# BTL_POWER.net
KiCad netlist of a schematic drawn in Altium Designer
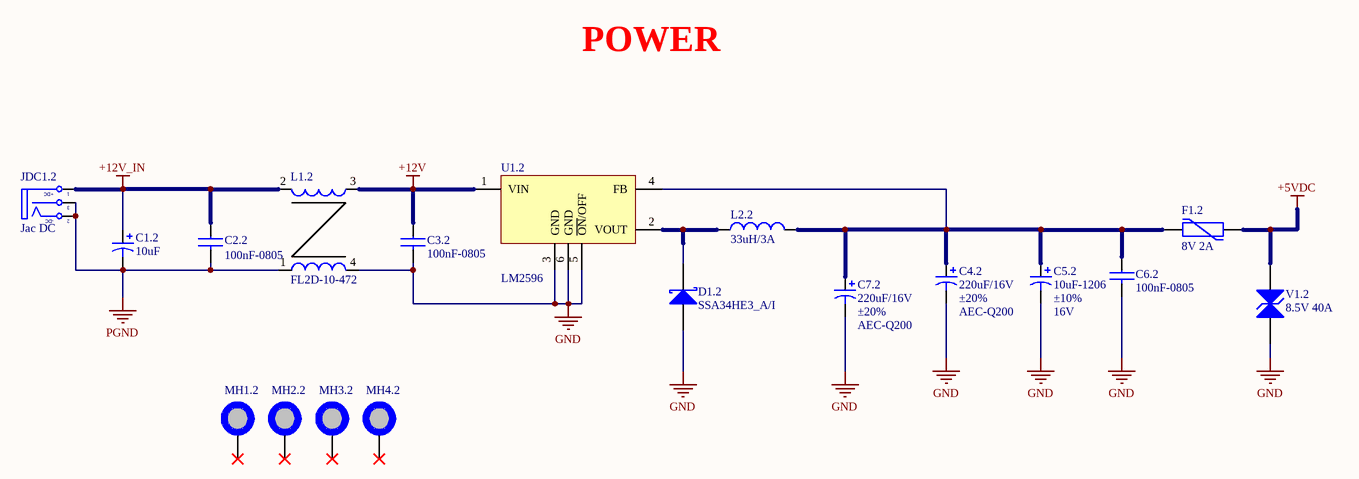
[diagram p0: BTL_POWER.SchDoc]

(export (version "E")
  (design (tool "Eeschema 10.0.6"))
  (components
    (comp (ref "C1.2")
      (value "10uF")
      (footprint "CAP_ALUMINUM_D8")
      (description "CAP ALUM 47UF 20% 16V SMD")
      (fields
        (field (name "MANUFACTURER") "Panasonic Electronic Components")
        (field (name "MANUFACTURER PART NUMBER") "EEE-FK1C470P")
      )
      (libsource (lib "Indruino") (part "EEE-FK1C470P"))
    )
    (comp (ref "C2.2")
      (value "100nF-0805")
      (footprint "CAP0805")
      (description "CAP CER 30PF 50V NPO 0805")
      (fields
        (field (name "MANUFACTURER") "Yageo")
        (field (name "MANUFACTURER PART NUMBER") "CC0805JRNPO9BN300")
      )
      (libsource (lib "Indruino") (part "CC0805JRNPO9BN300"))
    )
    (comp (ref "C3.2")
      (value "100nF-0805")
      (footprint "CAP0805")
      (description "CAP CER 30PF 50V NPO 0805")
      (fields
        (field (name "MANUFACTURER") "Yageo")
        (field (name "MANUFACTURER PART NUMBER") "CC0805JRNPO9BN300")
      )
      (libsource (lib "Indruino") (part "CC0805JRNPO9BN300"))
    )
    (comp (ref "C4.2")
      (value "220uF/16V")
      (footprint "CAP_ALUMINUM_D8")
      (description "CAP ALUM 47UF 20% 16V SMD")
      (fields
        (field (name "MANUFACTURER") "Panasonic Electronic Components")
        (field (name "MANUFACTURER PART NUMBER") "EEE-FK1C470P")
        (field (name "TOLERANCE") "±20%")
        (field (name "RATINGS") "AEC-Q200")
      )
      (libsource (lib "Indruino") (part "EEE-FK1C470P"))
    )
    (comp (ref "C5.2")
      (value "10uF-1206")
      (footprint "CAP1206_TANTALUM_YELLOW")
      (description "CAP TANT 10UF 16V 10% 1206")
      (fields (field (name "TOLERANCE") "±10%") (field (name "VOLTAGE - RATED") "16V"))
      (libsource (lib "Indruino") (part "T491A106K016AT"))
    )
    (comp (ref "C6.2")
      (value "100nF-0805")
      (footprint "CAP0805")
      (description "CAP CER 30PF 50V NPO 0805")
      (fields
        (field (name "MANUFACTURER") "Yageo")
        (field (name "MANUFACTURER PART NUMBER") "CC0805JRNPO9BN300")
      )
      (libsource (lib "Indruino") (part "CC0805JRNPO9BN300"))
    )
    (comp (ref "C7.2")
      (value "220uF/16V")
      (footprint "CAP_ALUMINUM_D8")
      (description "CAP ALUM 47UF 20% 16V SMD")
      (fields
        (field (name "MANUFACTURER") "Panasonic Electronic Components")
        (field (name "MANUFACTURER PART NUMBER") "EEE-FK1C470P")
        (field (name "TOLERANCE") "±20%")
        (field (name "RATINGS") "AEC-Q200")
      )
      (libsource (lib "Indruino") (part "EEE-FK1C470P"))
    )
    (comp (ref "D1.2")
      (value "SSA34HE3_A/I")
      (footprint "DO-214AC")
      (description "DIODE SCHOTTKY 40V 3A DO214AC")
      (libsource (lib "Indruino") (part "DIODE_SSA34HE3_A/I"))
    )
    (comp (ref "F1.2")
      (value "8V 2A")
      (footprint "Indruino:FUSE_PTC_SMD1812_03")
      (description "PTC RESET FUSE 8V 2A 1812")
      (fields (field (name "MANUFACTURER") "Bourns") (field (name "MANUFACTURER PART NUMBER") "MF-MSMF200-2"))
      (libsource (lib "Indruino") (part "FUSE_MF-MSMF200-2"))
    )
    (comp (ref "JDC1.2")
      (value "Jac DC")
      (footprint "MinhTien_PcbLib:DC-IN")
      (description "Jac DC input")
      (libsource (lib "MinhTien_SCHLib") (part "DCIN"))
    )
    (comp (ref "L1.2")
      (value "FL2D-10-472")
      (footprint "INDC_FL2D-10-472")
      (description "4.7uH, 1A")
      (libsource (lib "Indruino") (part "IND_FL2D-10-472"))
    )
    (comp (ref "L2.2")
      (value "33uH/3A")
      (footprint "INDC_CDRH8D28")
      (description "FIXED IND 10UH 3.2A 47 MOHM SMD")
      (fields
        (field (name "MANUFACTURER") "Sumida America Components Inc.")
        (field (name "MANUFACTURER PART NUMBER") "CDRH8D28NP-100NC")
      )
      (libsource (lib "Indruino") (part "IND_CDRH8D28NP-100NC"))
    )
    (comp (ref "MH1.2")
      (value "MH_5MMC_3.2MMD")
      (footprint "MH_5MMD_3.2MMD")
      (description "Mounting Hole 5mm Diameter, 3.2mm Drill")
      (libsource (lib "Indruino") (part "MH_5MMC_3.2MMD"))
    )
    (comp (ref "MH2.2")
      (value "MH_5MMC_3.2MMD")
      (footprint "MH_5MMD_3.2MMD")
      (description "Mounting Hole 5mm Diameter, 3.2mm Drill")
      (libsource (lib "Indruino") (part "MH_5MMC_3.2MMD"))
    )
    (comp (ref "MH3.2")
      (value "MH_5MMC_3.2MMD")
      (footprint "MH_5MMD_3.2MMD")
      (description "Mounting Hole 5mm Diameter, 3.2mm Drill")
      (libsource (lib "Indruino") (part "MH_5MMC_3.2MMD"))
    )
    (comp (ref "MH4.2")
      (value "MH_5MMC_3.2MMD")
      (footprint "MH_5MMD_3.2MMD")
      (description "Mounting Hole 5mm Diameter, 3.2mm Drill")
      (libsource (lib "Indruino") (part "MH_5MMC_3.2MMD"))
    )
    (comp (ref "U1.2")
      (value "LM2596")
      (footprint "MinhTien_PcbLib:TO263-5")
      (description "1A Regulator")
      (libsource (lib "MinhTien_SCHLib") (part "LM2596"))
    )
    (comp (ref "V1.2")
      (value "8.5V 40A")
      (footprint "Indruino:INDC0805")
      (description "VARISTOR 8.5V 40A 0805")
      (fields
        (field (name "MANUFACTURER") "Kyocera AVX")
        (field (name "MANUFACTURER PART NUMBER") "VC080505A150RP")
      )
      (libsource (lib "Indruino") (part "VARISTOR_VC080505A150RP"))
    )
  )
  (nets
    (net (code "1") (name "+5VDC") (class "Default")
      (node (ref "F1.2") (pin "2") (pinfunction "2_2") (pintype "passive"))
      (node (ref "V1.2") (pin "1") (pinfunction "1_1") (pintype "passive"))
    )
    (net (code "2") (name "+12V") (class "Default")
      (node (ref "C3.2") (pin "1") (pinfunction "1_1") (pintype "passive"))
      (node (ref "L1.2") (pin "3") (pinfunction "3_3") (pintype "passive"))
      (node (ref "U1.2") (pin "1") (pinfunction "VIN_1") (pintype "passive"))
    )
    (net (code "3") (name "+12V_IN") (class "Default")
      (node (ref "C1.2") (pin "1") (pinfunction "1_1") (pintype "passive"))
      (node (ref "C2.2") (pin "1") (pinfunction "1_1") (pintype "passive"))
      (node (ref "JDC1.2") (pin "1") (pinfunction "T_1") (pintype "passive"))
      (node (ref "L1.2") (pin "2") (pinfunction "2_2") (pintype "passive"))
    )
    (net (code "4") (name "GND") (class "Default")
      (node (ref "C3.2") (pin "2") (pinfunction "2_2") (pintype "passive"))
      (node (ref "C4.2") (pin "2") (pinfunction "2_2") (pintype "passive"))
      (node (ref "C5.2") (pin "2") (pinfunction "2_2") (pintype "passive"))
      (node (ref "C6.2") (pin "2") (pinfunction "2_2") (pintype "passive"))
      (node (ref "C7.2") (pin "2") (pinfunction "2_2") (pintype "passive"))
      (node (ref "D1.2") (pin "1") (pinfunction "A_1") (pintype "passive"))
      (node (ref "L1.2") (pin "4") (pinfunction "4_4") (pintype "passive"))
      (node (ref "U1.2") (pin "3") (pinfunction "GND_3") (pintype "passive"))
      (node (ref "U1.2") (pin "5") (pinfunction "~{ON}/OFF_5") (pintype "passive"))
      (node (ref "U1.2") (pin "6") (pinfunction "GND_6") (pintype "passive"))
      (node (ref "V1.2") (pin "2") (pinfunction "2_2") (pintype "passive"))
    )
    (net (code "5") (name "Net-(D1.2-K)") (class "Default")
      (node (ref "D1.2") (pin "2") (pinfunction "K_2") (pintype "passive"))
      (node (ref "L2.2") (pin "1") (pinfunction "1_1") (pintype "passive"))
      (node (ref "U1.2") (pin "2") (pinfunction "VOUT_2") (pintype "passive"))
    )
    (net (code "6") (name "Net-(U1.2-FB)") (class "Default")
      (node (ref "C4.2") (pin "1") (pinfunction "1_1") (pintype "passive"))
      (node (ref "C5.2") (pin "1") (pinfunction "1_1") (pintype "passive"))
      (node (ref "C6.2") (pin "1") (pinfunction "1_1") (pintype "passive"))
      (node (ref "C7.2") (pin "1") (pinfunction "1_1") (pintype "passive"))
      (node (ref "F1.2") (pin "1") (pinfunction "1_1") (pintype "passive"))
      (node (ref "L2.2") (pin "2") (pinfunction "2_2") (pintype "passive"))
      (node (ref "U1.2") (pin "4") (pinfunction "FB_4") (pintype "passive"))
    )
    (net (code "7") (name "PGND") (class "Default")
      (node (ref "C1.2") (pin "2") (pinfunction "2_2") (pintype "passive"))
      (node (ref "C2.2") (pin "2") (pinfunction "2_2") (pintype "passive"))
      (node (ref "JDC1.2") (pin "2") (pinfunction "TN_2") (pintype "passive"))
      (node (ref "JDC1.2") (pin "3") (pinfunction "S_3") (pintype "power_in"))
      (node (ref "L1.2") (pin "1") (pinfunction "1_1") (pintype "passive"))
    )
    (net (code "8") (name "unconnected-(MH1.2-Pad1)") (class "Default")
      (node (ref "MH1.2") (pin "1") (pinfunction "1_1") (pintype "passive+no_connect"))
    )
    (net (code "9") (name "unconnected-(MH2.2-Pad1)") (class "Default")
      (node (ref "MH2.2") (pin "1") (pinfunction "1_1") (pintype "passive+no_connect"))
    )
    (net (code "10") (name "unconnected-(MH3.2-Pad1)") (class "Default")
      (node (ref "MH3.2") (pin "1") (pinfunction "1_1") (pintype "passive+no_connect"))
    )
    (net (code "11") (name "unconnected-(MH4.2-Pad1)") (class "Default")
      (node (ref "MH4.2") (pin "1") (pinfunction "1_1") (pintype "passive+no_connect"))
    )
  )
)
